# Shield_try1.net
KiCad netlist of a schematic drawn in EAGLE
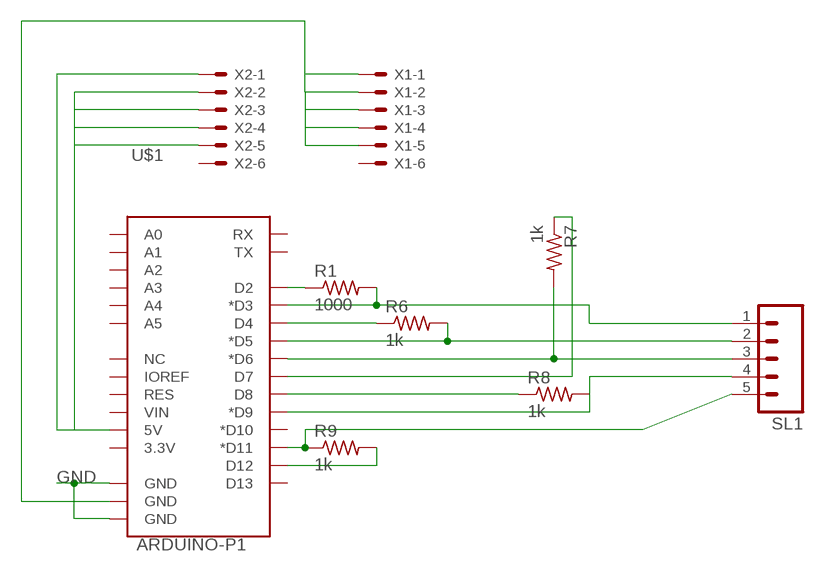
[diagram p0: schematic, sheet 1]

(export (version "E")
  (design (tool "Eeschema 10.0.6"))
  (components
    (comp (ref "R1")
      (value "1000")
      (footprint "eagle-import:R0805")
      (libsource (lib "eagle-import") (part "R-US_R0805"))
    )
    (comp (ref "R6")
      (value "1k")
      (footprint "eagle-import:R0805")
      (libsource (lib "eagle-import") (part "R-US_R0805"))
    )
    (comp (ref "R7")
      (value "1k")
      (footprint "eagle-import:R0805")
      (libsource (lib "eagle-import") (part "R-US_R0805"))
    )
    (comp (ref "R8")
      (value "1k")
      (footprint "eagle-import:R0805")
      (libsource (lib "eagle-import") (part "R-US_R0805"))
    )
    (comp (ref "R9")
      (value "1k")
      (footprint "eagle-import:R0805")
      (libsource (lib "eagle-import") (part "R-US_R0805"))
    )
    (comp (ref "SL1")
      (value "M05")
      (footprint "eagle-import:05P")
      (libsource (lib "eagle-import") (part "M05"))
    )
    (comp (ref "U$1")
      (value "ARDUINO-P1")
      (footprint "eagle-import:ARDUINO-P1")
      (libsource (lib "eagle-import") (part "ARDUINO-P1"))
    )
    (comp (ref "X1")
      (value "22-23-2061")
      (footprint "eagle-import:22-23-2061")
      (fields (field (name "MF") "MOLEX"))
      (libsource (lib "eagle-import") (part "22-23-2061"))
    )
    (comp (ref "X2")
      (value "22-23-2061")
      (footprint "eagle-import:22-23-2061")
      (fields (field (name "MF") "MOLEX"))
      (libsource (lib "eagle-import") (part "22-23-2061"))
    )
  )
  (nets
    (net (code "1") (name "/GND") (class "Default")
      (node (ref "U$1") (pin "GND@0") (pinfunction "GND_GND@0") (pintype "bidirectional"))
      (node (ref "U$1") (pin "GND@1") (pinfunction "GND_GND@1") (pintype "bidirectional"))
      (node (ref "U$1") (pin "GND@2") (pinfunction "GND_GND@2") (pintype "bidirectional"))
      (node (ref "X1") (pin "1") (pinfunction "S_1") (pintype "passive"))
      (node (ref "X1") (pin "2") (pinfunction "S_2") (pintype "passive"))
      (node (ref "X1") (pin "3") (pinfunction "S_3") (pintype "passive"))
      (node (ref "X1") (pin "4") (pinfunction "S_4") (pintype "passive"))
      (node (ref "X1") (pin "5") (pinfunction "S_5") (pintype "passive"))
    )
    (net (code "2") (name "Net-(R1-Pad1)") (class "Default")
      (node (ref "R1") (pin "1") (pinfunction "1_1") (pintype "passive"))
      (node (ref "U$1") (pin "D2") (pinfunction "D2_D2") (pintype "bidirectional"))
    )
    (net (code "3") (name "Net-(R6-Pad1)") (class "Default")
      (node (ref "R6") (pin "1") (pinfunction "1_1") (pintype "passive"))
      (node (ref "U$1") (pin "D4") (pinfunction "D4_D4") (pintype "bidirectional"))
    )
    (net (code "4") (name "Net-(R7-Pad1)") (class "Default")
      (node (ref "R7") (pin "1") (pinfunction "1_1") (pintype "passive"))
      (node (ref "U$1") (pin "D7") (pinfunction "D7_D7") (pintype "bidirectional"))
    )
    (net (code "5") (name "Net-(R8-Pad1)") (class "Default")
      (node (ref "R8") (pin "1") (pinfunction "1_1") (pintype "passive"))
      (node (ref "U$1") (pin "D8") (pinfunction "D8_D8") (pintype "bidirectional"))
    )
    (net (code "6") (name "Net-(R9-Pad2)") (class "Default")
      (node (ref "R9") (pin "2") (pinfunction "2_2") (pintype "passive"))
      (node (ref "U$1") (pin "D12") (pinfunction "D12_D12") (pintype "bidirectional"))
    )
    (net (code "7") (name "Net-(U$1-*D3)") (class "Default")
      (node (ref "R1") (pin "2") (pinfunction "2_2") (pintype "passive"))
      (node (ref "SL1") (pin "1") (pinfunction "1_1") (pintype "passive"))
      (node (ref "U$1") (pin "D3") (pinfunction "*D3_D3") (pintype "bidirectional"))
    )
    (net (code "8") (name "Net-(U$1-*D5)") (class "Default")
      (node (ref "R6") (pin "2") (pinfunction "2_2") (pintype "passive"))
      (node (ref "SL1") (pin "2") (pinfunction "2_2") (pintype "passive"))
      (node (ref "U$1") (pin "D5") (pinfunction "*D5_D5") (pintype "bidirectional"))
    )
    (net (code "9") (name "Net-(U$1-*D6)") (class "Default")
      (node (ref "R7") (pin "2") (pinfunction "2_2") (pintype "passive"))
      (node (ref "SL1") (pin "3") (pinfunction "3_3") (pintype "passive"))
      (node (ref "U$1") (pin "D6") (pinfunction "*D6_D6") (pintype "bidirectional"))
    )
    (net (code "10") (name "Net-(U$1-*D9)") (class "Default")
      (node (ref "R8") (pin "2") (pinfunction "2_2") (pintype "passive"))
      (node (ref "SL1") (pin "4") (pinfunction "4_4") (pintype "passive"))
      (node (ref "U$1") (pin "D9") (pinfunction "*D9_D9") (pintype "bidirectional"))
    )
    (net (code "11") (name "Net-(U$1-*D11)") (class "Default")
      (node (ref "R9") (pin "1") (pinfunction "1_1") (pintype "passive"))
      (node (ref "SL1") (pin "5") (pinfunction "5_5") (pintype "passive"))
      (node (ref "U$1") (pin "D11") (pinfunction "*D11_D11") (pintype "bidirectional"))
    )
    (net (code "12") (name "Net-(X2A-S)") (class "Default")
      (node (ref "U$1") (pin "5V") (pinfunction "5V_5V") (pintype "bidirectional"))
      (node (ref "X2") (pin "1") (pinfunction "S_1") (pintype "passive"))
      (node (ref "X2") (pin "2") (pinfunction "S_2") (pintype "passive"))
      (node (ref "X2") (pin "3") (pinfunction "S_3") (pintype "passive"))
      (node (ref "X2") (pin "4") (pinfunction "S_4") (pintype "passive"))
      (node (ref "X2") (pin "5") (pinfunction "S_5") (pintype "passive"))
    )
    (net (code "13") (name "unconnected-(U$1-*D10-PadD10)") (class "Default")
      (node (ref "U$1") (pin "D10") (pinfunction "*D10_D10") (pintype "bidirectional"))
    )
    (net (code "14") (name "unconnected-(U$1-Pad3.3V)") (class "Default")
      (node (ref "U$1") (pin "3.3V") (pinfunction "3.3V_3.3V") (pintype "bidirectional"))
    )
    (net (code "15") (name "unconnected-(U$1-PadA0)") (class "Default")
      (node (ref "U$1") (pin "A0") (pinfunction "A0_A0") (pintype "bidirectional"))
    )
    (net (code "16") (name "unconnected-(U$1-PadA1)") (class "Default")
      (node (ref "U$1") (pin "A1") (pinfunction "A1_A1") (pintype "bidirectional"))
    )
    (net (code "17") (name "unconnected-(U$1-PadA2)") (class "Default")
      (node (ref "U$1") (pin "A2") (pinfunction "A2_A2") (pintype "bidirectional"))
    )
    (net (code "18") (name "unconnected-(U$1-PadA3)") (class "Default")
      (node (ref "U$1") (pin "A3") (pinfunction "A3_A3") (pintype "bidirectional"))
    )
    (net (code "19") (name "unconnected-(U$1-PadA4)") (class "Default")
      (node (ref "U$1") (pin "A4") (pinfunction "A4_A4") (pintype "bidirectional"))
    )
    (net (code "20") (name "unconnected-(U$1-PadA5)") (class "Default")
      (node (ref "U$1") (pin "A5") (pinfunction "A5_A5") (pintype "bidirectional"))
    )
    (net (code "21") (name "unconnected-(U$1-PadD13)") (class "Default")
      (node (ref "U$1") (pin "D13") (pinfunction "D13_D13") (pintype "bidirectional"))
    )
    (net (code "22") (name "unconnected-(U$1-PadIOREF)") (class "Default")
      (node (ref "U$1") (pin "IOREF") (pinfunction "IOREF_IOREF") (pintype "bidirectional"))
    )
    (net (code "23") (name "unconnected-(U$1-PadNC)") (class "Default")
      (node (ref "U$1") (pin "NC") (pinfunction "NC_NC") (pintype "bidirectional"))
    )
    (net (code "24") (name "unconnected-(U$1-PadRES)") (class "Default")
      (node (ref "U$1") (pin "RES") (pinfunction "RES_RES") (pintype "bidirectional"))
    )
    (net (code "25") (name "unconnected-(U$1-PadRX)") (class "Default")
      (node (ref "U$1") (pin "RX") (pinfunction "RX_RX") (pintype "bidirectional"))
    )
    (net (code "26") (name "unconnected-(U$1-PadTX)") (class "Default")
      (node (ref "U$1") (pin "TX") (pinfunction "TX_TX") (pintype "bidirectional"))
    )
    (net (code "27") (name "unconnected-(U$1-PadVIN)") (class "Default")
      (node (ref "U$1") (pin "VIN") (pinfunction "VIN_VIN") (pintype "bidirectional"))
    )
    (net (code "28") (name "unconnected-(X1F-S-Pad6)") (class "Default")
      (node (ref "X1") (pin "6") (pinfunction "S_6") (pintype "passive"))
    )
    (net (code "29") (name "unconnected-(X2F-S-Pad6)") (class "Default")
      (node (ref "X2") (pin "6") (pinfunction "S_6") (pintype "passive"))
    )
  )
)
